# ncp-1117-inverted.net
KiCad netlist of a schematic drawn in EAGLE
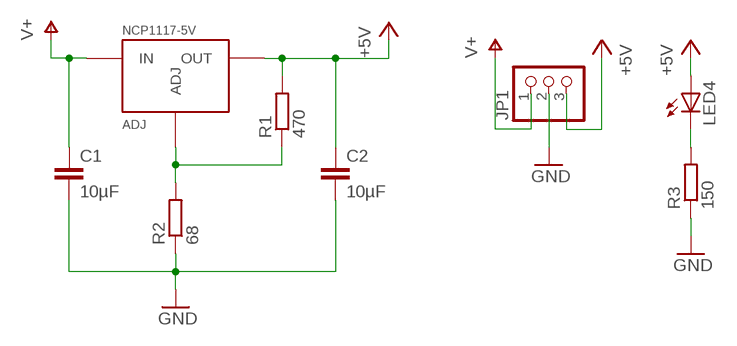
[diagram p0: schematic, sheet 1]

(export (version "E")
  (design (tool "Eeschema 10.0.6"))
  (components
    (comp (ref "C1")
      (value "10µF")
      (footprint "eagle-import:C0805")
      (libsource (lib "eagle-import") (part "C-EUC0805"))
    )
    (comp (ref "C2")
      (value "10µF")
      (footprint "eagle-import:C0805")
      (libsource (lib "eagle-import") (part "C-EUC0805"))
    )
    (comp (ref "JP1")
      (value "PINHD-1X3")
      (footprint "eagle-import:1X03")
      (libsource (lib "eagle-import") (part "PINHD-1X3"))
    )
    (comp (ref "LED4")
      (value "LEDCHIP-LED0603")
      (footprint "eagle-import:CHIP-LED0603")
      (libsource (lib "eagle-import") (part "LEDCHIP-LED0603"))
    )
    (comp (ref "NCP1117-5V")
      (value "ADJ")
      (footprint "eagle-import:TO252")
      (libsource (lib "eagle-import") (part "REGULATOR-TLV1117TO-252"))
    )
    (comp (ref "R1")
      (value "470")
      (footprint "eagle-import:R0603")
      (libsource (lib "eagle-import") (part "R-EU_R0603"))
    )
    (comp (ref "R2")
      (value "68")
      (footprint "eagle-import:R0603")
      (libsource (lib "eagle-import") (part "R-EU_R0603"))
    )
    (comp (ref "R3")
      (value "150")
      (footprint "eagle-import:R0603")
      (libsource (lib "eagle-import") (part "R-EU_R0603"))
    )
  )
  (nets
    (net (code "1") (name "+5V") (class "Default")
      (node (ref "C2") (pin "1") (pinfunction "1_1") (pintype "passive"))
      (node (ref "JP1") (pin "3") (pinfunction "3_3") (pintype "passive"))
      (node (ref "LED4") (pin "A") (pinfunction "A_A") (pintype "passive"))
      (node (ref "NCP1117-5V") (pin "3") (pinfunction "OUT_3") (pintype "bidirectional"))
      (node (ref "R1") (pin "2") (pinfunction "2_2") (pintype "passive"))
    )
    (net (code "2") (name "GND") (class "Default")
      (node (ref "C1") (pin "2") (pinfunction "2_2") (pintype "passive"))
      (node (ref "C2") (pin "2") (pinfunction "2_2") (pintype "passive"))
      (node (ref "JP1") (pin "2") (pinfunction "2_2") (pintype "passive"))
      (node (ref "R2") (pin "1") (pinfunction "1_1") (pintype "passive"))
      (node (ref "R3") (pin "1") (pinfunction "1_1") (pintype "passive"))
    )
    (net (code "3") (name "Net-(LED4-PadC)") (class "Default")
      (node (ref "LED4") (pin "C") (pinfunction "C_C") (pintype "passive"))
      (node (ref "R3") (pin "2") (pinfunction "2_2") (pintype "passive"))
    )
    (net (code "4") (name "Net-(NCP1117-5V-ADJ)") (class "Default")
      (node (ref "NCP1117-5V") (pin "1") (pinfunction "ADJ_1") (pintype "bidirectional"))
      (node (ref "R1") (pin "1") (pinfunction "1_1") (pintype "passive"))
      (node (ref "R2") (pin "2") (pinfunction "2_2") (pintype "passive"))
    )
    (net (code "5") (name "V+") (class "Default")
      (node (ref "C1") (pin "1") (pinfunction "1_1") (pintype "passive"))
      (node (ref "JP1") (pin "1") (pinfunction "1_1") (pintype "passive"))
      (node (ref "NCP1117-5V") (pin "2") (pinfunction "IN_2") (pintype "bidirectional"))
    )
  )
)
